# Enlighten-PL9823.net
KiCad netlist of a schematic drawn in EAGLE
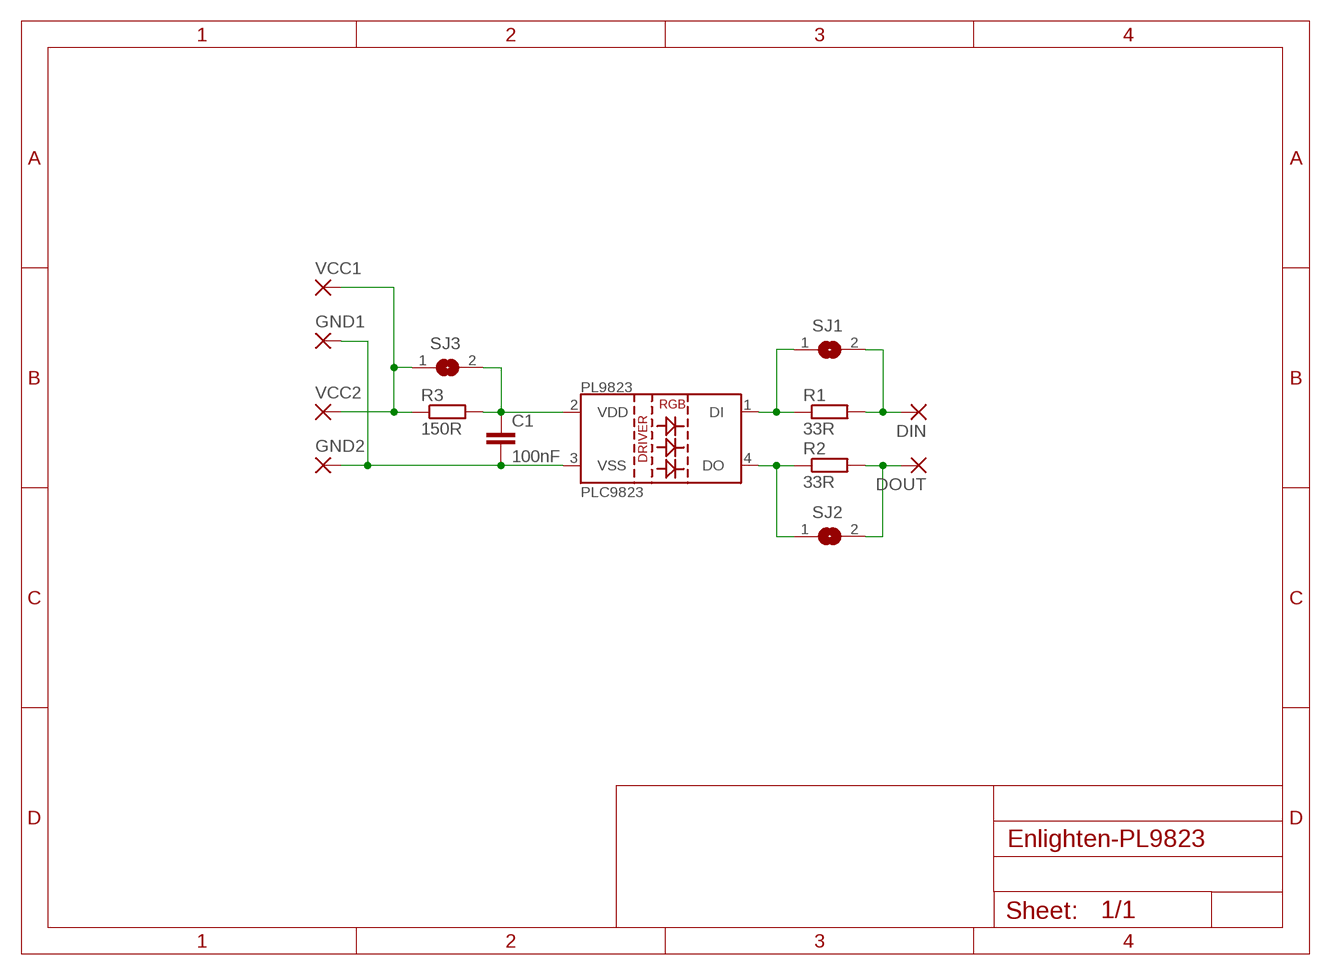
[diagram p0: schematic, sheet 1]

(export (version "E")
  (design (tool "Eeschema 10.0.6"))
  (components
    (comp (ref "C1")
      (value "100nF")
      (footprint "eagle-import:C025-024X044")
      (libsource (lib "eagle-import") (part "C-EU025-024X044"))
    )
    (comp (ref "DIN")
      (value "SMD2")
      (footprint "eagle-import:SMD1,27-2,54")
      (libsource (lib "eagle-import") (part "SMD2"))
    )
    (comp (ref "DOUT")
      (value "SMD2")
      (footprint "eagle-import:SMD1,27-2,54")
      (libsource (lib "eagle-import") (part "SMD2"))
    )
    (comp (ref "GND1")
      (value "SMD5")
      (footprint "eagle-import:SMD2,54-5,08")
      (libsource (lib "eagle-import") (part "SMD5"))
    )
    (comp (ref "GND2")
      (value "SMD5")
      (footprint "eagle-import:SMD2,54-5,08")
      (libsource (lib "eagle-import") (part "SMD5"))
    )
    (comp (ref "PLC9823")
      (value "LED-PL9823-F5W")
      (footprint "eagle-import:LED-PL9823-F5W")
      (libsource (lib "eagle-import") (part "LED-PL9823-F5W"))
    )
    (comp (ref "R1")
      (value "33R")
      (footprint "eagle-import:0207_10")
      (libsource (lib "eagle-import") (part "R-EU_0207/10"))
    )
    (comp (ref "R2")
      (value "33R")
      (footprint "eagle-import:0207_10")
      (libsource (lib "eagle-import") (part "R-EU_0207/10"))
    )
    (comp (ref "R3")
      (value "150R")
      (footprint "eagle-import:0207_10")
      (libsource (lib "eagle-import") (part "R-EU_0207/10"))
    )
    (comp (ref "SJ1") (value "SJ") (footprint "eagle-import:SJ") (libsource (lib "eagle-import") (part "SJ")))
    (comp (ref "SJ2") (value "SJ") (footprint "eagle-import:SJ") (libsource (lib "eagle-import") (part "SJ")))
    (comp (ref "SJ3") (value "SJ") (footprint "eagle-import:SJ") (libsource (lib "eagle-import") (part "SJ")))
    (comp (ref "VCC1")
      (value "SMD5")
      (footprint "eagle-import:SMD2,54-5,08")
      (libsource (lib "eagle-import") (part "SMD5"))
    )
    (comp (ref "VCC2")
      (value "SMD5")
      (footprint "eagle-import:SMD2,54-5,08")
      (libsource (lib "eagle-import") (part "SMD5"))
    )
  )
  (nets
    (net (code "1") (name "Net-(DIN-P)") (class "Default")
      (node (ref "DIN") (pin "1") (pinfunction "P_1") (pintype "passive"))
      (node (ref "R1") (pin "2") (pinfunction "2_2") (pintype "passive"))
      (node (ref "SJ1") (pin "2") (pinfunction "2_2") (pintype "passive"))
    )
    (net (code "2") (name "Net-(DOUT-P)") (class "Default")
      (node (ref "DOUT") (pin "1") (pinfunction "P_1") (pintype "passive"))
      (node (ref "R2") (pin "2") (pinfunction "2_2") (pintype "passive"))
      (node (ref "SJ2") (pin "2") (pinfunction "2_2") (pintype "passive"))
    )
    (net (code "3") (name "Net-(GND1-P)") (class "Default")
      (node (ref "C1") (pin "2") (pinfunction "2_2") (pintype "passive"))
      (node (ref "GND1") (pin "1") (pinfunction "P_1") (pintype "passive"))
      (node (ref "GND2") (pin "1") (pinfunction "P_1") (pintype "passive"))
      (node (ref "PLC9823") (pin "3") (pinfunction "VSS_3") (pintype "bidirectional"))
    )
    (net (code "4") (name "Net-(PLC9823-DI)") (class "Default")
      (node (ref "PLC9823") (pin "1") (pinfunction "DI_1") (pintype "bidirectional"))
      (node (ref "R1") (pin "1") (pinfunction "1_1") (pintype "passive"))
      (node (ref "SJ1") (pin "1") (pinfunction "1_1") (pintype "passive"))
    )
    (net (code "5") (name "Net-(PLC9823-DO)") (class "Default")
      (node (ref "PLC9823") (pin "4") (pinfunction "DO_4") (pintype "bidirectional"))
      (node (ref "R2") (pin "1") (pinfunction "1_1") (pintype "passive"))
      (node (ref "SJ2") (pin "1") (pinfunction "1_1") (pintype "passive"))
    )
    (net (code "6") (name "Net-(PLC9823-VDD)") (class "Default")
      (node (ref "C1") (pin "1") (pinfunction "1_1") (pintype "passive"))
      (node (ref "PLC9823") (pin "2") (pinfunction "VDD_2") (pintype "bidirectional"))
      (node (ref "R3") (pin "2") (pinfunction "2_2") (pintype "passive"))
      (node (ref "SJ3") (pin "2") (pinfunction "2_2") (pintype "passive"))
    )
    (net (code "7") (name "Net-(VCC1-P)") (class "Default")
      (node (ref "R3") (pin "1") (pinfunction "1_1") (pintype "passive"))
      (node (ref "SJ3") (pin "1") (pinfunction "1_1") (pintype "passive"))
      (node (ref "VCC1") (pin "1") (pinfunction "P_1") (pintype "passive"))
      (node (ref "VCC2") (pin "1") (pinfunction "P_1") (pintype "passive"))
    )
  )
)
